# MasterHMI.net
KiCad netlist of a schematic drawn in EAGLE
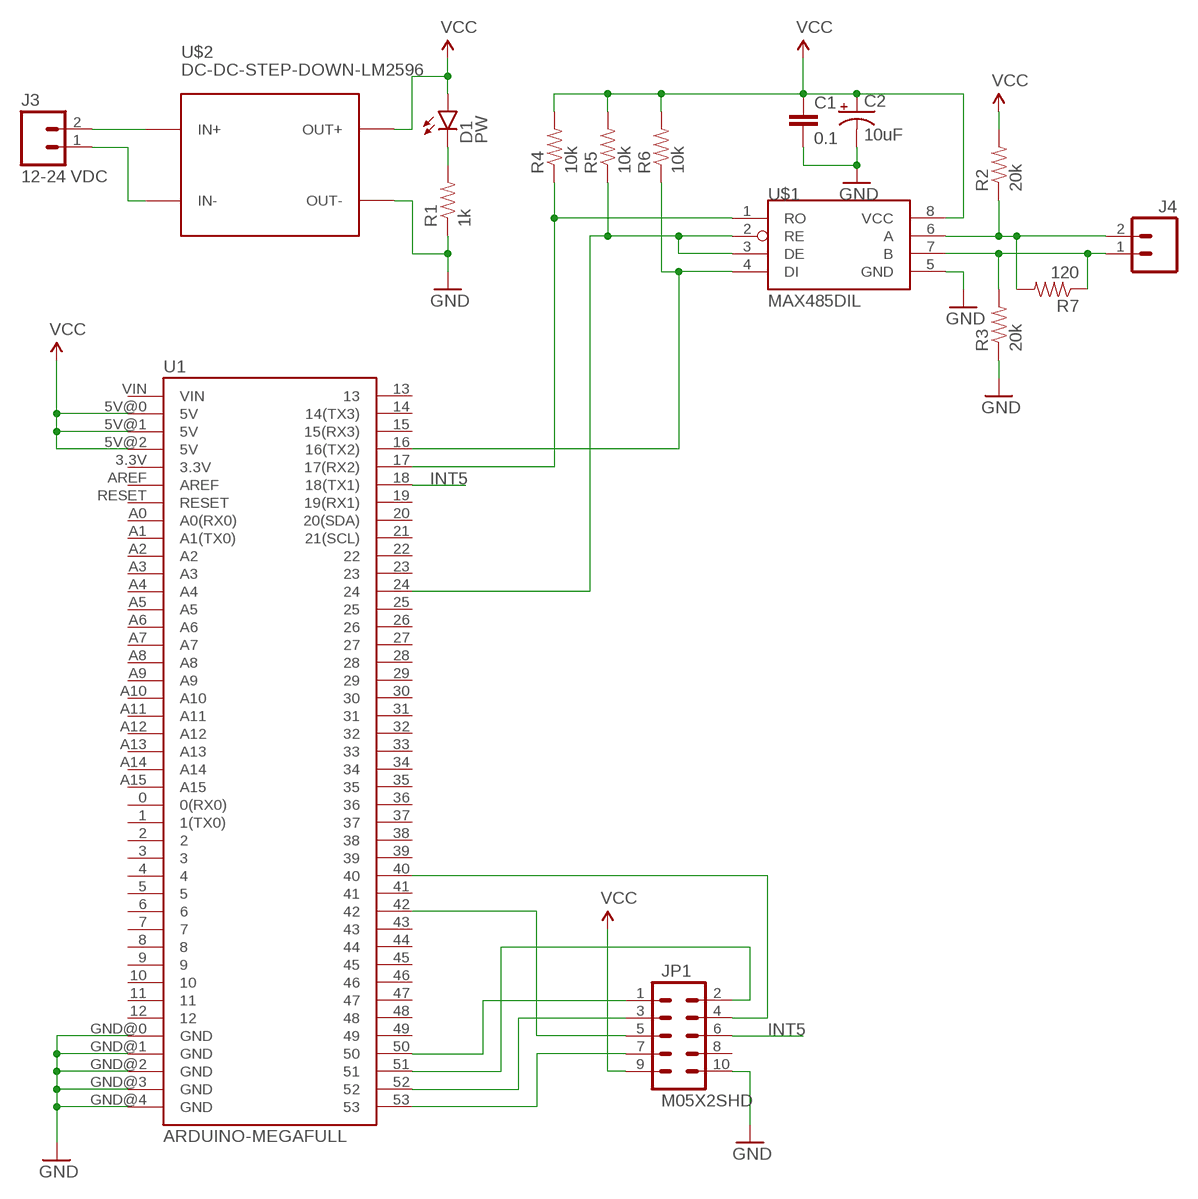
[diagram p0: schematic, sheet 1]

(export (version "E")
  (design (tool "Eeschema 10.0.6"))
  (components
    (comp (ref "C1")
      (value "0.1")
      (footprint "eagle-import:CAP-PTH-5MM")
      (libsource (lib "eagle-import") (part "CAPPTH1"))
    )
    (comp (ref "C2")
      (value "10uF")
      (footprint "eagle-import:CPOL-RADIAL-10UF-25V")
      (libsource (lib "eagle-import") (part "CAP_POLPTH2"))
    )
    (comp (ref "D1")
      (value "PW")
      (footprint "eagle-import:LED3MM")
      (libsource (lib "eagle-import") (part "LED3MM"))
    )
    (comp (ref "J3")
      (value "12-24 VDC")
      (footprint "eagle-import:SCREWTERMINAL-5MM-2")
      (libsource (lib "eagle-import") (part "M025MM"))
    )
    (comp (ref "J4")
      (value "M025MM")
      (footprint "eagle-import:SCREWTERMINAL-5MM-2")
      (libsource (lib "eagle-import") (part "M025MM"))
    )
    (comp (ref "JP1")
      (value "M05X2SHD")
      (footprint "eagle-import:2X5-SHROUDED")
      (libsource (lib "eagle-import") (part "M05X2SHD"))
    )
    (comp (ref "R1")
      (value "1k")
      (footprint "eagle-import:AXIAL-0.3")
      (libsource (lib "eagle-import") (part "RESISTORAXIAL-0.3"))
    )
    (comp (ref "R2")
      (value "20k")
      (footprint "eagle-import:AXIAL-0.3")
      (libsource (lib "eagle-import") (part "RESISTORAXIAL-0.3"))
    )
    (comp (ref "R3")
      (value "20k")
      (footprint "eagle-import:AXIAL-0.3")
      (libsource (lib "eagle-import") (part "RESISTORAXIAL-0.3"))
    )
    (comp (ref "R4")
      (value "10k")
      (footprint "eagle-import:AXIAL-0.3")
      (libsource (lib "eagle-import") (part "RESISTORAXIAL-0.3"))
    )
    (comp (ref "R5")
      (value "10k")
      (footprint "eagle-import:AXIAL-0.3")
      (libsource (lib "eagle-import") (part "RESISTORAXIAL-0.3"))
    )
    (comp (ref "R6")
      (value "10k")
      (footprint "eagle-import:AXIAL-0.3")
      (libsource (lib "eagle-import") (part "RESISTORAXIAL-0.3"))
    )
    (comp (ref "R7")
      (value "120")
      (footprint "eagle-import:AXIAL-0.3")
      (libsource (lib "eagle-import") (part "RESISTORAXIAL-0.3"))
    )
    (comp (ref "U$1")
      (value "MAX485DIL")
      (footprint "eagle-import:DIL08")
      (libsource (lib "eagle-import") (part "MAX485DIL"))
    )
    (comp (ref "U$2")
      (value "DC-DC-STEP-DOWN-LM2596")
      (footprint "eagle-import:DC-DC-STEP-DOWN-LM2596")
      (libsource (lib "eagle-import") (part "DC-DC-STEP-DOWN-LM2596"))
    )
    (comp (ref "U1")
      (value "ARDUINO-MEGAFULL")
      (footprint "eagle-import:ARDUINO_MEGA")
      (libsource (lib "eagle-import") (part "ARDUINO-MEGAFULL"))
    )
  )
  (nets
    (net (code "1") (name "/INT5") (class "Default")
      (node (ref "JP1") (pin "6") (pinfunction "6_6") (pintype "passive"))
      (node (ref "U1") (pin "18") (pinfunction "18(TX1)_18") (pintype "bidirectional"))
    )
    (net (code "2") (name "GND") (class "Default")
      (node (ref "C1") (pin "2") (pinfunction "2_2") (pintype "passive"))
      (node (ref "C2") (pin "2") (pinfunction "-_2") (pintype "passive"))
      (node (ref "JP1") (pin "10") (pinfunction "10_10") (pintype "passive"))
      (node (ref "R1") (pin "P$1") (pinfunction "1_P$1") (pintype "passive"))
      (node (ref "R3") (pin "P$1") (pinfunction "1_P$1") (pintype "passive"))
      (node (ref "U$1") (pin "5") (pinfunction "GND_5") (pintype "bidirectional"))
      (node (ref "U$2") (pin "OUT-") (pinfunction "OUT-_OUT-") (pintype "bidirectional"))
      (node (ref "U1") (pin "GND@0") (pinfunction "GND_GND@0") (pintype "bidirectional"))
      (node (ref "U1") (pin "GND@1") (pinfunction "GND_GND@1") (pintype "bidirectional"))
      (node (ref "U1") (pin "GND@2") (pinfunction "GND_GND@2") (pintype "bidirectional"))
      (node (ref "U1") (pin "GND@3") (pinfunction "GND_GND@3") (pintype "bidirectional"))
      (node (ref "U1") (pin "GND@4") (pinfunction "GND_GND@4") (pintype "bidirectional"))
    )
    (net (code "3") (name "Net-(D1-C)") (class "Default")
      (node (ref "D1") (pin "K") (pinfunction "C_K") (pintype "passive"))
      (node (ref "R1") (pin "P$2") (pinfunction "2_P$2") (pintype "passive"))
    )
    (net (code "4") (name "Net-(J3-Pad1)") (class "Default")
      (node (ref "J3") (pin "1") (pinfunction "1_1") (pintype "passive"))
      (node (ref "U$2") (pin "IN-") (pinfunction "IN-_IN-") (pintype "bidirectional"))
    )
    (net (code "5") (name "Net-(J3-Pad2)") (class "Default")
      (node (ref "J3") (pin "2") (pinfunction "2_2") (pintype "passive"))
      (node (ref "U$2") (pin "IN+") (pinfunction "IN+_IN+") (pintype "bidirectional"))
    )
    (net (code "6") (name "Net-(JP1-Pad1)") (class "Default")
      (node (ref "JP1") (pin "1") (pinfunction "1_1") (pintype "passive"))
      (node (ref "U1") (pin "50") (pinfunction "50_50") (pintype "bidirectional"))
    )
    (net (code "7") (name "Net-(JP1-Pad2)") (class "Default")
      (node (ref "JP1") (pin "2") (pinfunction "2_2") (pintype "passive"))
      (node (ref "U1") (pin "51") (pinfunction "51_51") (pintype "bidirectional"))
    )
    (net (code "8") (name "Net-(JP1-Pad3)") (class "Default")
      (node (ref "JP1") (pin "3") (pinfunction "3_3") (pintype "passive"))
      (node (ref "U1") (pin "52") (pinfunction "52_52") (pintype "bidirectional"))
    )
    (net (code "9") (name "Net-(JP1-Pad4)") (class "Default")
      (node (ref "JP1") (pin "4") (pinfunction "4_4") (pintype "passive"))
      (node (ref "U1") (pin "40") (pinfunction "40_40") (pintype "bidirectional"))
    )
    (net (code "10") (name "Net-(JP1-Pad5)") (class "Default")
      (node (ref "JP1") (pin "5") (pinfunction "5_5") (pintype "passive"))
      (node (ref "U1") (pin "42") (pinfunction "42_42") (pintype "bidirectional"))
    )
    (net (code "11") (name "Net-(JP1-Pad7)") (class "Default")
      (node (ref "JP1") (pin "7") (pinfunction "7_7") (pintype "passive"))
      (node (ref "U1") (pin "53") (pinfunction "53_53") (pintype "bidirectional"))
    )
    (net (code "12") (name "Net-(R2-1)") (class "Default")
      (node (ref "J4") (pin "2") (pinfunction "2_2") (pintype "passive"))
      (node (ref "R2") (pin "P$1") (pinfunction "1_P$1") (pintype "passive"))
      (node (ref "R7") (pin "P$2") (pinfunction "2_P$2") (pintype "passive"))
      (node (ref "U$1") (pin "6") (pinfunction "A_6") (pintype "bidirectional"))
    )
    (net (code "13") (name "Net-(R3-2)") (class "Default")
      (node (ref "J4") (pin "1") (pinfunction "1_1") (pintype "passive"))
      (node (ref "R3") (pin "P$2") (pinfunction "2_P$2") (pintype "passive"))
      (node (ref "R7") (pin "P$1") (pinfunction "1_P$1") (pintype "passive"))
      (node (ref "U$1") (pin "7") (pinfunction "B_7") (pintype "bidirectional"))
    )
    (net (code "14") (name "Net-(R4-1)") (class "Default")
      (node (ref "R4") (pin "P$1") (pinfunction "1_P$1") (pintype "passive"))
      (node (ref "U$1") (pin "1") (pinfunction "RO_1") (pintype "bidirectional"))
      (node (ref "U1") (pin "17") (pinfunction "17(RX2)_17") (pintype "bidirectional"))
    )
    (net (code "15") (name "Net-(R5-1)") (class "Default")
      (node (ref "R5") (pin "P$1") (pinfunction "1_P$1") (pintype "passive"))
      (node (ref "U$1") (pin "2") (pinfunction "RE_2") (pintype "bidirectional"))
      (node (ref "U$1") (pin "3") (pinfunction "DE_3") (pintype "bidirectional"))
      (node (ref "U1") (pin "24") (pinfunction "24_24") (pintype "bidirectional"))
    )
    (net (code "16") (name "Net-(R6-1)") (class "Default")
      (node (ref "R6") (pin "P$1") (pinfunction "1_P$1") (pintype "passive"))
      (node (ref "U$1") (pin "4") (pinfunction "DI_4") (pintype "bidirectional"))
      (node (ref "U1") (pin "16") (pinfunction "16(TX2)_16") (pintype "bidirectional"))
    )
    (net (code "17") (name "VCC") (class "Default")
      (node (ref "C1") (pin "1") (pinfunction "1_1") (pintype "passive"))
      (node (ref "C2") (pin "1") (pinfunction "+_1") (pintype "passive"))
      (node (ref "D1") (pin "A") (pinfunction "A_A") (pintype "passive"))
      (node (ref "JP1") (pin "9") (pinfunction "9_9") (pintype "passive"))
      (node (ref "R2") (pin "P$2") (pinfunction "2_P$2") (pintype "passive"))
      (node (ref "R4") (pin "P$2") (pinfunction "2_P$2") (pintype "passive"))
      (node (ref "R5") (pin "P$2") (pinfunction "2_P$2") (pintype "passive"))
      (node (ref "R6") (pin "P$2") (pinfunction "2_P$2") (pintype "passive"))
      (node (ref "U$1") (pin "8") (pinfunction "VCC_8") (pintype "bidirectional"))
      (node (ref "U$2") (pin "OUT+") (pinfunction "OUT+_OUT+") (pintype "bidirectional"))
      (node (ref "U1") (pin "5V@0") (pinfunction "5V_5V@0") (pintype "bidirectional"))
      (node (ref "U1") (pin "5V@1") (pinfunction "5V_5V@1") (pintype "bidirectional"))
      (node (ref "U1") (pin "5V@2") (pinfunction "5V_5V@2") (pintype "bidirectional"))
    )
    (net (code "18") (name "unconnected-(JP1-Pad8)") (class "Default")
      (node (ref "JP1") (pin "8") (pinfunction "8_8") (pintype "passive"))
    )
    (net (code "19") (name "unconnected-(U1-0(RX0)-Pad0)") (class "Default")
      (node (ref "U1") (pin "0") (pinfunction "0(RX0)_0") (pintype "bidirectional"))
    )
    (net (code "20") (name "unconnected-(U1-1(TX0)-Pad1)") (class "Default")
      (node (ref "U1") (pin "1") (pinfunction "1(TX0)_1") (pintype "bidirectional"))
    )
    (net (code "21") (name "unconnected-(U1-14(TX3)-Pad14)") (class "Default")
      (node (ref "U1") (pin "14") (pinfunction "14(TX3)_14") (pintype "bidirectional"))
    )
    (net (code "22") (name "unconnected-(U1-15(RX3)-Pad15)") (class "Default")
      (node (ref "U1") (pin "15") (pinfunction "15(RX3)_15") (pintype "bidirectional"))
    )
    (net (code "23") (name "unconnected-(U1-19(RX1)-Pad19)") (class "Default")
      (node (ref "U1") (pin "19") (pinfunction "19(RX1)_19") (pintype "bidirectional"))
    )
    (net (code "24") (name "unconnected-(U1-20(SDA)-Pad20)") (class "Default")
      (node (ref "U1") (pin "20") (pinfunction "20(SDA)_20") (pintype "bidirectional"))
    )
    (net (code "25") (name "unconnected-(U1-21(SCL)-Pad21)") (class "Default")
      (node (ref "U1") (pin "21") (pinfunction "21(SCL)_21") (pintype "bidirectional"))
    )
    (net (code "26") (name "unconnected-(U1-A0(RX0)-PadA0)") (class "Default")
      (node (ref "U1") (pin "A0") (pinfunction "A0(RX0)_A0") (pintype "bidirectional"))
    )
    (net (code "27") (name "unconnected-(U1-A1(TX0)-PadA1)") (class "Default")
      (node (ref "U1") (pin "A1") (pinfunction "A1(TX0)_A1") (pintype "bidirectional"))
    )
    (net (code "28") (name "unconnected-(U1-Pad2)") (class "Default")
      (node (ref "U1") (pin "2") (pinfunction "2_2") (pintype "bidirectional"))
    )
    (net (code "29") (name "unconnected-(U1-Pad3)") (class "Default")
      (node (ref "U1") (pin "3") (pinfunction "3_3") (pintype "bidirectional"))
    )
    (net (code "30") (name "unconnected-(U1-Pad3.3V)") (class "Default")
      (node (ref "U1") (pin "3.3V") (pinfunction "3.3V_3.3V") (pintype "bidirectional"))
    )
    (net (code "31") (name "unconnected-(U1-Pad4)") (class "Default")
      (node (ref "U1") (pin "4") (pinfunction "4_4") (pintype "bidirectional"))
    )
    (net (code "32") (name "unconnected-(U1-Pad5)") (class "Default")
      (node (ref "U1") (pin "5") (pinfunction "5_5") (pintype "bidirectional"))
    )
    (net (code "33") (name "unconnected-(U1-Pad6)") (class "Default")
      (node (ref "U1") (pin "6") (pinfunction "6_6") (pintype "bidirectional"))
    )
    (net (code "34") (name "unconnected-(U1-Pad7)") (class "Default")
      (node (ref "U1") (pin "7") (pinfunction "7_7") (pintype "bidirectional"))
    )
    (net (code "35") (name "unconnected-(U1-Pad8)") (class "Default")
      (node (ref "U1") (pin "8") (pinfunction "8_8") (pintype "bidirectional"))
    )
    (net (code "36") (name "unconnected-(U1-Pad9)") (class "Default")
      (node (ref "U1") (pin "9") (pinfunction "9_9") (pintype "bidirectional"))
    )
    (net (code "37") (name "unconnected-(U1-Pad10)") (class "Default")
      (node (ref "U1") (pin "10") (pinfunction "10_10") (pintype "bidirectional"))
    )
    (net (code "38") (name "unconnected-(U1-Pad11)") (class "Default")
      (node (ref "U1") (pin "11") (pinfunction "11_11") (pintype "bidirectional"))
    )
    (net (code "39") (name "unconnected-(U1-Pad12)") (class "Default")
      (node (ref "U1") (pin "12") (pinfunction "12_12") (pintype "bidirectional"))
    )
    (net (code "40") (name "unconnected-(U1-Pad13)") (class "Default")
      (node (ref "U1") (pin "13") (pinfunction "13_13") (pintype "bidirectional"))
    )
    (net (code "41") (name "unconnected-(U1-Pad22)") (class "Default")
      (node (ref "U1") (pin "22") (pinfunction "22_22") (pintype "bidirectional"))
    )
    (net (code "42") (name "unconnected-(U1-Pad23)") (class "Default")
      (node (ref "U1") (pin "23") (pinfunction "23_23") (pintype "bidirectional"))
    )
    (net (code "43") (name "unconnected-(U1-Pad25)") (class "Default")
      (node (ref "U1") (pin "25") (pinfunction "25_25") (pintype "bidirectional"))
    )
    (net (code "44") (name "unconnected-(U1-Pad26)") (class "Default")
      (node (ref "U1") (pin "26") (pinfunction "26_26") (pintype "bidirectional"))
    )
    (net (code "45") (name "unconnected-(U1-Pad27)") (class "Default")
      (node (ref "U1") (pin "27") (pinfunction "27_27") (pintype "bidirectional"))
    )
    (net (code "46") (name "unconnected-(U1-Pad28)") (class "Default")
      (node (ref "U1") (pin "28") (pinfunction "28_28") (pintype "bidirectional"))
    )
    (net (code "47") (name "unconnected-(U1-Pad29)") (class "Default")
      (node (ref "U1") (pin "29") (pinfunction "29_29") (pintype "bidirectional"))
    )
    (net (code "48") (name "unconnected-(U1-Pad30)") (class "Default")
      (node (ref "U1") (pin "30") (pinfunction "30_30") (pintype "bidirectional"))
    )
    (net (code "49") (name "unconnected-(U1-Pad31)") (class "Default")
      (node (ref "U1") (pin "31") (pinfunction "31_31") (pintype "bidirectional"))
    )
    (net (code "50") (name "unconnected-(U1-Pad32)") (class "Default")
      (node (ref "U1") (pin "32") (pinfunction "32_32") (pintype "bidirectional"))
    )
    (net (code "51") (name "unconnected-(U1-Pad33)") (class "Default")
      (node (ref "U1") (pin "33") (pinfunction "33_33") (pintype "bidirectional"))
    )
    (net (code "52") (name "unconnected-(U1-Pad34)") (class "Default")
      (node (ref "U1") (pin "34") (pinfunction "34_34") (pintype "bidirectional"))
    )
    (net (code "53") (name "unconnected-(U1-Pad35)") (class "Default")
      (node (ref "U1") (pin "35") (pinfunction "35_35") (pintype "bidirectional"))
    )
    (net (code "54") (name "unconnected-(U1-Pad36)") (class "Default")
      (node (ref "U1") (pin "36") (pinfunction "36_36") (pintype "bidirectional"))
    )
    (net (code "55") (name "unconnected-(U1-Pad37)") (class "Default")
      (node (ref "U1") (pin "37") (pinfunction "37_37") (pintype "bidirectional"))
    )
    (net (code "56") (name "unconnected-(U1-Pad38)") (class "Default")
      (node (ref "U1") (pin "38") (pinfunction "38_38") (pintype "bidirectional"))
    )
    (net (code "57") (name "unconnected-(U1-Pad39)") (class "Default")
      (node (ref "U1") (pin "39") (pinfunction "39_39") (pintype "bidirectional"))
    )
    (net (code "58") (name "unconnected-(U1-Pad41)") (class "Default")
      (node (ref "U1") (pin "41") (pinfunction "41_41") (pintype "bidirectional"))
    )
    (net (code "59") (name "unconnected-(U1-Pad43)") (class "Default")
      (node (ref "U1") (pin "43") (pinfunction "43_43") (pintype "bidirectional"))
    )
    (net (code "60") (name "unconnected-(U1-Pad44)") (class "Default")
      (node (ref "U1") (pin "44") (pinfunction "44_44") (pintype "bidirectional"))
    )
    (net (code "61") (name "unconnected-(U1-Pad45)") (class "Default")
      (node (ref "U1") (pin "45") (pinfunction "45_45") (pintype "bidirectional"))
    )
    (net (code "62") (name "unconnected-(U1-Pad46)") (class "Default")
      (node (ref "U1") (pin "46") (pinfunction "46_46") (pintype "bidirectional"))
    )
    (net (code "63") (name "unconnected-(U1-Pad47)") (class "Default")
      (node (ref "U1") (pin "47") (pinfunction "47_47") (pintype "bidirectional"))
    )
    (net (code "64") (name "unconnected-(U1-Pad48)") (class "Default")
      (node (ref "U1") (pin "48") (pinfunction "48_48") (pintype "bidirectional"))
    )
    (net (code "65") (name "unconnected-(U1-Pad49)") (class "Default")
      (node (ref "U1") (pin "49") (pinfunction "49_49") (pintype "bidirectional"))
    )
    (net (code "66") (name "unconnected-(U1-PadA2)") (class "Default")
      (node (ref "U1") (pin "A2") (pinfunction "A2_A2") (pintype "bidirectional"))
    )
    (net (code "67") (name "unconnected-(U1-PadA3)") (class "Default")
      (node (ref "U1") (pin "A3") (pinfunction "A3_A3") (pintype "bidirectional"))
    )
    (net (code "68") (name "unconnected-(U1-PadA4)") (class "Default")
      (node (ref "U1") (pin "A4") (pinfunction "A4_A4") (pintype "bidirectional"))
    )
    (net (code "69") (name "unconnected-(U1-PadA5)") (class "Default")
      (node (ref "U1") (pin "A5") (pinfunction "A5_A5") (pintype "bidirectional"))
    )
    (net (code "70") (name "unconnected-(U1-PadA6)") (class "Default")
      (node (ref "U1") (pin "A6") (pinfunction "A6_A6") (pintype "bidirectional"))
    )
    (net (code "71") (name "unconnected-(U1-PadA7)") (class "Default")
      (node (ref "U1") (pin "A7") (pinfunction "A7_A7") (pintype "bidirectional"))
    )
    (net (code "72") (name "unconnected-(U1-PadA8)") (class "Default")
      (node (ref "U1") (pin "A8") (pinfunction "A8_A8") (pintype "bidirectional"))
    )
    (net (code "73") (name "unconnected-(U1-PadA9)") (class "Default")
      (node (ref "U1") (pin "A9") (pinfunction "A9_A9") (pintype "bidirectional"))
    )
    (net (code "74") (name "unconnected-(U1-PadA10)") (class "Default")
      (node (ref "U1") (pin "A10") (pinfunction "A10_A10") (pintype "bidirectional"))
    )
    (net (code "75") (name "unconnected-(U1-PadA11)") (class "Default")
      (node (ref "U1") (pin "A11") (pinfunction "A11_A11") (pintype "bidirectional"))
    )
    (net (code "76") (name "unconnected-(U1-PadA12)") (class "Default")
      (node (ref "U1") (pin "A12") (pinfunction "A12_A12") (pintype "bidirectional"))
    )
    (net (code "77") (name "unconnected-(U1-PadA13)") (class "Default")
      (node (ref "U1") (pin "A13") (pinfunction "A13_A13") (pintype "bidirectional"))
    )
    (net (code "78") (name "unconnected-(U1-PadA14)") (class "Default")
      (node (ref "U1") (pin "A14") (pinfunction "A14_A14") (pintype "bidirectional"))
    )
    (net (code "79") (name "unconnected-(U1-PadA15)") (class "Default")
      (node (ref "U1") (pin "A15") (pinfunction "A15_A15") (pintype "bidirectional"))
    )
    (net (code "80") (name "unconnected-(U1-PadAREF)") (class "Default")
      (node (ref "U1") (pin "AREF") (pinfunction "AREF_AREF") (pintype "bidirectional"))
    )
    (net (code "81") (name "unconnected-(U1-PadRESET)") (class "Default")
      (node (ref "U1") (pin "RESET") (pinfunction "RESET_RESET") (pintype "bidirectional"))
    )
    (net (code "82") (name "unconnected-(U1-PadVIN)") (class "Default")
      (node (ref "U1") (pin "VIN") (pinfunction "VIN_VIN") (pintype "bidirectional"))
    )
  )
)
